# motorfilter.net
KiCad netlist of a schematic drawn in EAGLE
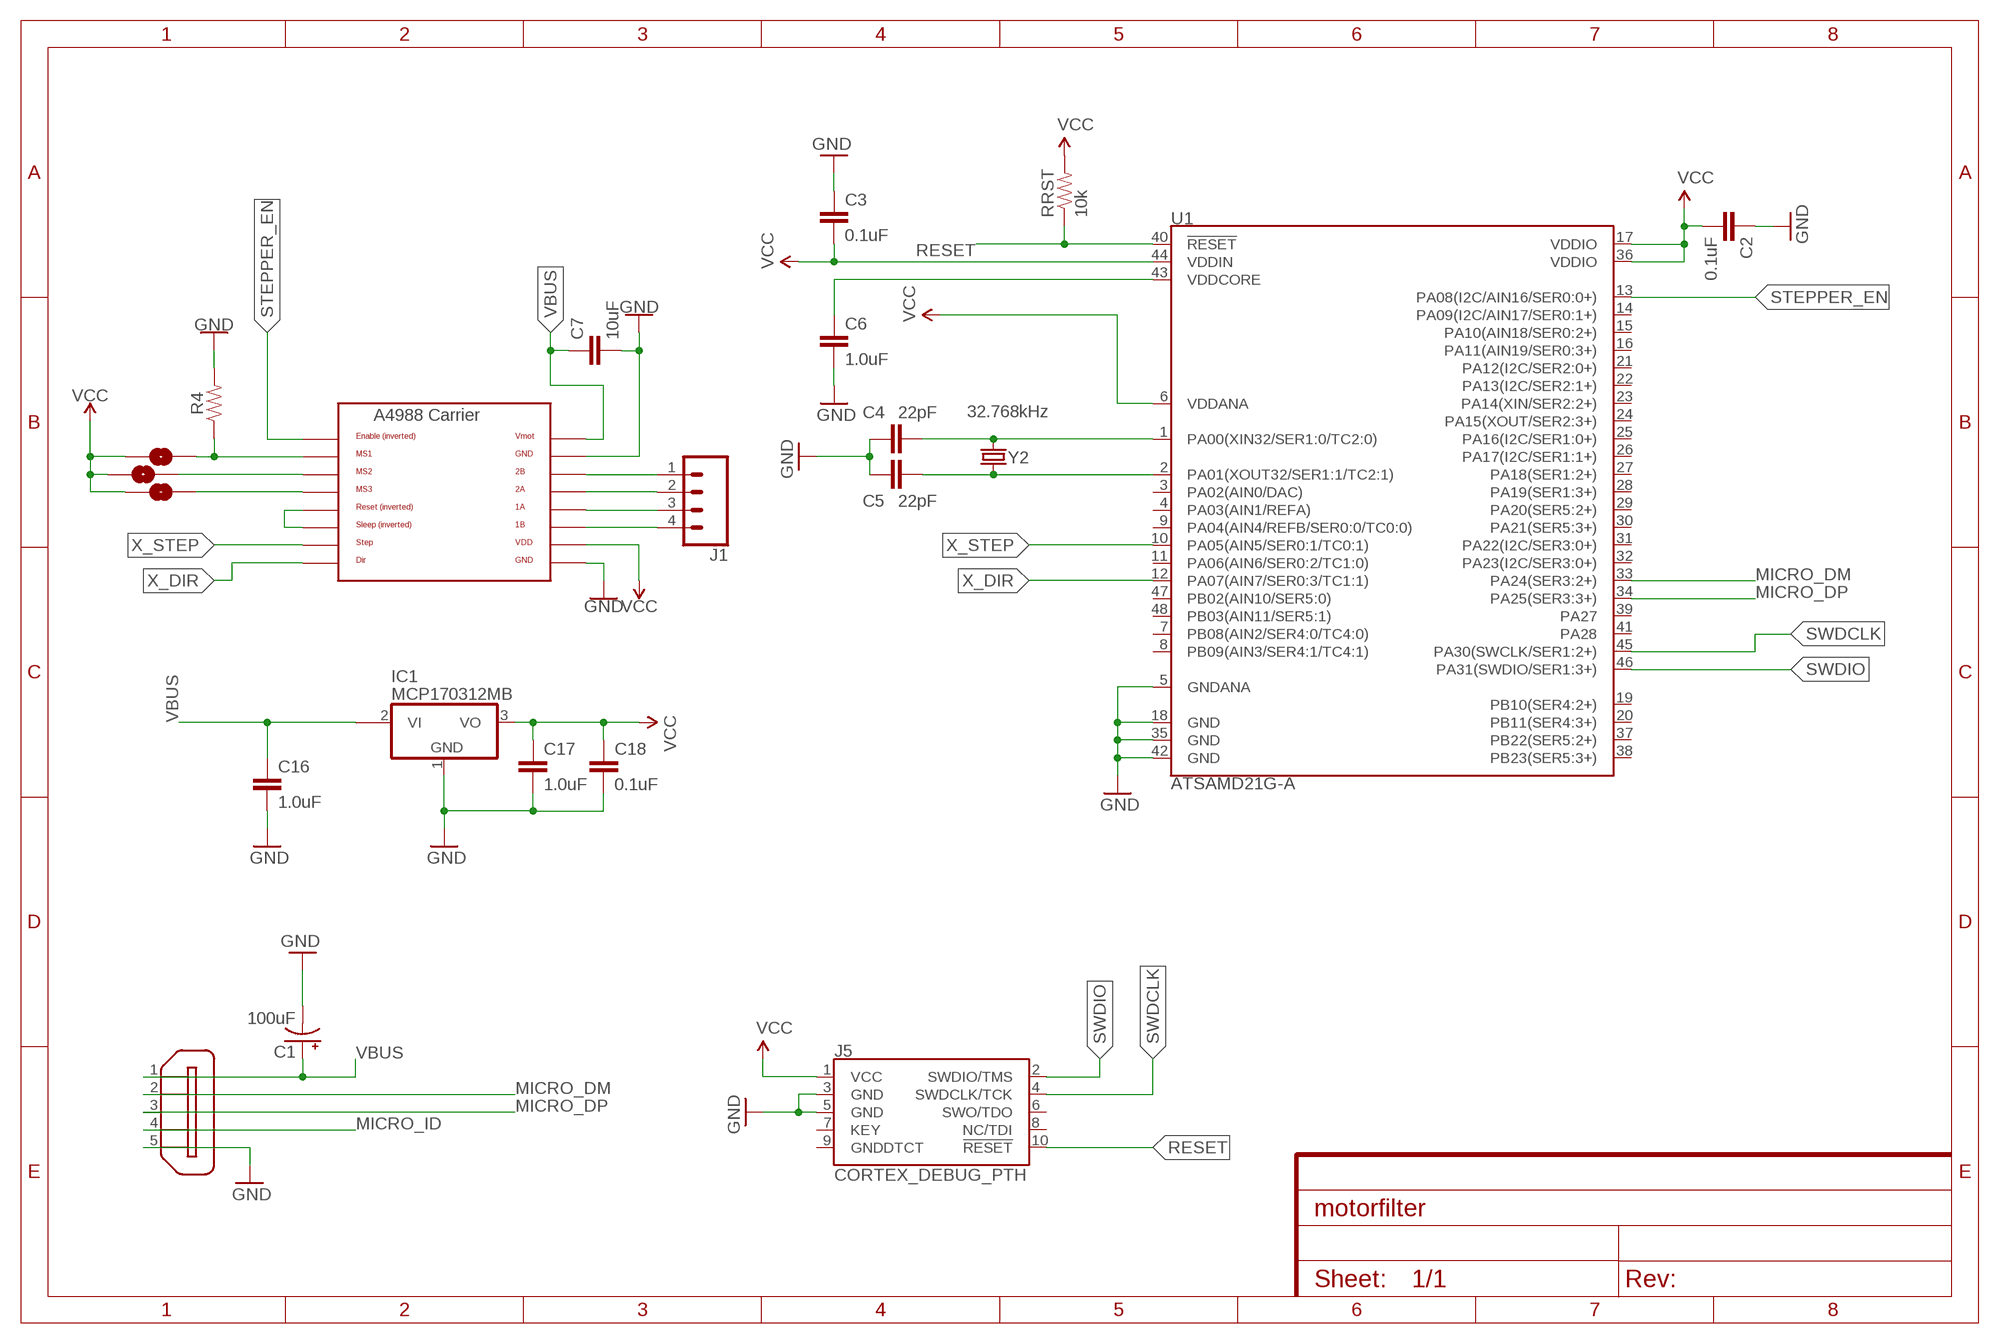
[diagram p0: schematic, sheet 1]

(export (version "E")
  (design (tool "Eeschema 10.0.6"))
  (components
    (comp (ref "C1")
      (value "100uF")
      (footprint "eagle-import:PANASONIC_D")
      (libsource (lib "eagle-import") (part "100UF-POLAR-25V-20%(ELEC)"))
    )
    (comp (ref "C2")
      (value "0.1uF")
      (footprint "eagle-import:0805")
      (libsource (lib "eagle-import") (part "1.0UF-0805-25V-10%"))
    )
    (comp (ref "C3")
      (value "0.1uF")
      (footprint "eagle-import:0805")
      (libsource (lib "eagle-import") (part "1.0UF-0805-25V-10%"))
    )
    (comp (ref "C4")
      (value "22pF")
      (footprint "eagle-import:0805")
      (libsource (lib "eagle-import") (part "CAP0805"))
    )
    (comp (ref "C5")
      (value "22pF")
      (footprint "eagle-import:0805")
      (libsource (lib "eagle-import") (part "CAP0805"))
    )
    (comp (ref "C6")
      (value "1.0uF")
      (footprint "eagle-import:0805")
      (libsource (lib "eagle-import") (part "1.0UF-0805-25V-10%"))
    )
    (comp (ref "C7")
      (value "10uF")
      (footprint "eagle-import:1206")
      (libsource (lib "eagle-import") (part "1.0UF-1206-50V-10%"))
    )
    (comp (ref "C16")
      (value "1.0uF")
      (footprint "eagle-import:0805")
      (libsource (lib "eagle-import") (part "1.0UF-0805-25V-10%"))
    )
    (comp (ref "C17")
      (value "1.0uF")
      (footprint "eagle-import:1206")
      (libsource (lib "eagle-import") (part "1.0UF-1206-50V-10%"))
    )
    (comp (ref "C18")
      (value "0.1uF")
      (footprint "eagle-import:0805")
      (libsource (lib "eagle-import") (part "1.0UF-0805-25V-10%"))
    )
    (comp (ref "IC1")
      (value "MCP170312MB")
      (footprint "eagle-import:SOT89")
      (libsource (lib "eagle-import") (part "MCP1703MB12"))
    )
    (comp (ref "J1")
      (value "CONN_04SCREW")
      (footprint "eagle-import:SCREWTERMINAL-3.5MM-4")
      (libsource (lib "eagle-import") (part "CONN_04SCREW"))
    )
    (comp (ref "J5")
      (value "CORTEX_DEBUG_PTH")
      (footprint "eagle-import:2X5-PTH-1.27MM")
      (libsource (lib "eagle-import") (part "CORTEX_DEBUG_PTH"))
    )
    (comp (ref "JP4")
      (value "JUMPER-SMT_2_NO_SILK_ROUND")
      (footprint "eagle-import:SMT-JUMPER_2_NO_SILK_ROUND")
      (libsource (lib "eagle-import") (part "JUMPER-SMT_2_NO_SILK_ROUND"))
    )
    (comp (ref "JP5")
      (value "JUMPER-SMT_2_NO_SILK_ROUND")
      (footprint "eagle-import:SMT-JUMPER_2_NO_SILK_ROUND")
      (libsource (lib "eagle-import") (part "JUMPER-SMT_2_NO_SILK_ROUND"))
    )
    (comp (ref "JP6")
      (value "JUMPER-SMT_2_NO_SILK_ROUND")
      (footprint "eagle-import:SMT-JUMPER_2_NO_SILK_ROUND")
      (libsource (lib "eagle-import") (part "JUMPER-SMT_2_NO_SILK_ROUND"))
    )
    (comp (ref "R4")
      (value "RESISTOR0805")
      (footprint "eagle-import:0805")
      (libsource (lib "eagle-import") (part "RESISTOR0805"))
    )
    (comp (ref "RRST")
      (value "10k")
      (footprint "eagle-import:0805")
      (libsource (lib "eagle-import") (part "RESISTOR0805-RES"))
    )
    (comp (ref "U$2")
      (value "A4988BREAKOUT")
      (footprint "eagle-import:A4988BREAKOUT")
      (libsource (lib "eagle-import") (part "A4988BREAKOUT"))
    )
    (comp (ref "U1")
      (value "ATSAMD21G-A")
      (footprint "eagle-import:TQFP-48")
      (libsource (lib "eagle-import") (part "ATSAMD21G-A"))
    )
    (comp (ref "X2")
      (value "ZX62D-B-5PA8")
      (footprint "eagle-import:ZX62D-B-5PA8")
      (fields (field (name "MF") "Hirose"))
      (libsource (lib "eagle-import") (part "ZX62D-B-5PA8"))
    )
    (comp (ref "Y2")
      (value "32.768kHz")
      (footprint "eagle-import:CRYSTAL-SMD-3.2X1.5MM")
      (libsource (lib "eagle-import") (part "CRYSTAL3.2X1.5MM"))
    )
  )
  (nets
    (net (code "1") (name "/MICRO_DM") (class "Default")
      (node (ref "U1") (pin "33") (pinfunction "PA24(SER3:2+)_33") (pintype "bidirectional"))
      (node (ref "X2") (pin "2") (pinfunction "2_2") (pintype "passive"))
    )
    (net (code "2") (name "/MICRO_DP") (class "Default")
      (node (ref "U1") (pin "34") (pinfunction "PA25(SER3:3+)_34") (pintype "bidirectional"))
      (node (ref "X2") (pin "3") (pinfunction "3_3") (pintype "passive"))
    )
    (net (code "3") (name "/MICRO_ID") (class "Default")
      (node (ref "X2") (pin "4") (pinfunction "4_4") (pintype "passive"))
    )
    (net (code "4") (name "GND") (class "Default")
      (node (ref "C1") (pin "-") (pinfunction "-_-") (pintype "passive"))
      (node (ref "C16") (pin "2") (pinfunction "2_2") (pintype "passive"))
      (node (ref "C17") (pin "2") (pinfunction "2_2") (pintype "passive"))
      (node (ref "C18") (pin "2") (pinfunction "2_2") (pintype "passive"))
      (node (ref "C2") (pin "1") (pinfunction "1_1") (pintype "passive"))
      (node (ref "C3") (pin "1") (pinfunction "1_1") (pintype "passive"))
      (node (ref "C4") (pin "1") (pinfunction "1_1") (pintype "passive"))
      (node (ref "C5") (pin "1") (pinfunction "1_1") (pintype "passive"))
      (node (ref "C6") (pin "2") (pinfunction "2_2") (pintype "passive"))
      (node (ref "C7") (pin "2") (pinfunction "2_2") (pintype "passive"))
      (node (ref "IC1") (pin "1") (pinfunction "GND_1") (pintype "passive"))
      (node (ref "J5") (pin "3") (pinfunction "GND_3") (pintype "bidirectional"))
      (node (ref "J5") (pin "5") (pinfunction "GND_5") (pintype "bidirectional"))
      (node (ref "R4") (pin "2") (pinfunction "2_2") (pintype "passive"))
      (node (ref "U$2") (pin "GND") (pinfunction "GND_GND") (pintype "power_in"))
      (node (ref "U$2") (pin "GND@0") (pinfunction "GND_GND@0") (pintype "power_in"))
      (node (ref "U1") (pin "18") (pinfunction "GND_18") (pintype "bidirectional"))
      (node (ref "U1") (pin "35") (pinfunction "GND_35") (pintype "bidirectional"))
      (node (ref "U1") (pin "42") (pinfunction "GND_42") (pintype "bidirectional"))
      (node (ref "U1") (pin "5") (pinfunction "GNDANA_5") (pintype "bidirectional"))
      (node (ref "X2") (pin "5") (pinfunction "5_5") (pintype "passive"))
    )
    (net (code "5") (name "Net-(J1-Pad1)") (class "Default")
      (node (ref "J1") (pin "1") (pinfunction "1_1") (pintype "passive"))
      (node (ref "U$2") (pin "2B") (pinfunction "2B_2B") (pintype "output"))
    )
    (net (code "6") (name "Net-(J1-Pad2)") (class "Default")
      (node (ref "J1") (pin "2") (pinfunction "2_2") (pintype "passive"))
      (node (ref "U$2") (pin "2A") (pinfunction "2A_2A") (pintype "output"))
    )
    (net (code "7") (name "Net-(J1-Pad3)") (class "Default")
      (node (ref "J1") (pin "3") (pinfunction "3_3") (pintype "passive"))
      (node (ref "U$2") (pin "1A") (pinfunction "1A_1A") (pintype "output"))
    )
    (net (code "8") (name "Net-(J1-Pad4)") (class "Default")
      (node (ref "J1") (pin "4") (pinfunction "4_4") (pintype "passive"))
      (node (ref "U$2") (pin "1B") (pinfunction "1B_1B") (pintype "output"))
    )
    (net (code "9") (name "Net-(JP4-Pad2)") (class "Default")
      (node (ref "JP4") (pin "2") (pinfunction "2_2") (pintype "passive"))
      (node (ref "R4") (pin "1") (pinfunction "1_1") (pintype "passive"))
      (node (ref "U$2") (pin "MS1") (pinfunction "MS1_MS1") (pintype "input"))
    )
    (net (code "10") (name "Net-(JP5-Pad2)") (class "Default")
      (node (ref "JP5") (pin "2") (pinfunction "2_2") (pintype "passive"))
      (node (ref "U$2") (pin "MS2") (pinfunction "MS2_MS2") (pintype "input"))
    )
    (net (code "11") (name "Net-(JP6-Pad2)") (class "Default")
      (node (ref "JP6") (pin "2") (pinfunction "2_2") (pintype "passive"))
      (node (ref "U$2") (pin "MS3") (pinfunction "MS3_MS3") (pintype "input"))
    )
    (net (code "12") (name "Net-(U$2-SLEEP)") (class "Default")
      (node (ref "U$2") (pin "RST") (pinfunction "RST_RST") (pintype "input"))
      (node (ref "U$2") (pin "SLP") (pinfunction "SLEEP_SLP") (pintype "input"))
    )
    (net (code "13") (name "Net-(U1-PA00(XIN32{slash}SER1:0{slash}TC2:0))") (class "Default")
      (node (ref "C4") (pin "2") (pinfunction "2_2") (pintype "passive"))
      (node (ref "U1") (pin "1") (pinfunction "PA00(XIN32/SER1:0/TC2:0)_1") (pintype "bidirectional"))
      (node (ref "Y2") (pin "P$2") (pinfunction "2_P$2") (pintype "passive"))
    )
    (net (code "14") (name "Net-(U1-PA01(XOUT32{slash}SER1:1{slash}TC2:1))") (class "Default")
      (node (ref "C5") (pin "2") (pinfunction "2_2") (pintype "passive"))
      (node (ref "U1") (pin "2") (pinfunction "PA01(XOUT32/SER1:1/TC2:1)_2") (pintype "bidirectional"))
      (node (ref "Y2") (pin "P$1") (pinfunction "1_P$1") (pintype "passive"))
    )
    (net (code "15") (name "Net-(U1-VDDCORE)") (class "Default")
      (node (ref "C6") (pin "1") (pinfunction "1_1") (pintype "passive"))
      (node (ref "U1") (pin "43") (pinfunction "VDDCORE_43") (pintype "bidirectional"))
    )
    (net (code "16") (name "RESET") (class "Default")
      (node (ref "J5") (pin "10") (pinfunction "~{RESET}_10") (pintype "bidirectional"))
      (node (ref "RRST") (pin "1") (pinfunction "1_1") (pintype "passive"))
      (node (ref "U1") (pin "40") (pinfunction "~{RESET}_40") (pintype "bidirectional"))
    )
    (net (code "17") (name "STEPPER_EN") (class "Default")
      (node (ref "U$2") (pin "EN") (pinfunction "EN_EN") (pintype "input"))
      (node (ref "U1") (pin "13") (pinfunction "PA08(I2C/AIN16/SER0:0+)_13") (pintype "bidirectional"))
    )
    (net (code "18") (name "SWDCLK") (class "Default")
      (node (ref "J5") (pin "4") (pinfunction "SWDCLK/TCK_4") (pintype "bidirectional"))
      (node (ref "U1") (pin "45") (pinfunction "PA30(SWCLK/SER1:2+)_45") (pintype "bidirectional"))
    )
    (net (code "19") (name "SWDIO") (class "Default")
      (node (ref "J5") (pin "2") (pinfunction "SWDIO/TMS_2") (pintype "bidirectional"))
      (node (ref "U1") (pin "46") (pinfunction "PA31(SWDIO/SER1:3+)_46") (pintype "bidirectional"))
    )
    (net (code "20") (name "VBUS") (class "Default")
      (node (ref "C1") (pin "+") (pinfunction "+_+") (pintype "passive"))
      (node (ref "C16") (pin "1") (pinfunction "1_1") (pintype "passive"))
      (node (ref "C7") (pin "1") (pinfunction "1_1") (pintype "passive"))
      (node (ref "IC1") (pin "2@1") (pinfunction "VI1_2@1") (pintype "input"))
      (node (ref "U$2") (pin "VMOT") (pinfunction "VMOT_VMOT") (pintype "power_in"))
      (node (ref "X2") (pin "1") (pinfunction "1_1") (pintype "passive"))
    )
    (net (code "21") (name "VCC") (class "Default")
      (node (ref "C17") (pin "1") (pinfunction "1_1") (pintype "passive"))
      (node (ref "C18") (pin "1") (pinfunction "1_1") (pintype "passive"))
      (node (ref "C2") (pin "2") (pinfunction "2_2") (pintype "passive"))
      (node (ref "C3") (pin "2") (pinfunction "2_2") (pintype "passive"))
      (node (ref "IC1") (pin "3") (pinfunction "VO_3") (pintype "passive"))
      (node (ref "J5") (pin "1") (pinfunction "VCC_1") (pintype "bidirectional"))
      (node (ref "JP4") (pin "1") (pinfunction "1_1") (pintype "passive"))
      (node (ref "JP5") (pin "1") (pinfunction "1_1") (pintype "passive"))
      (node (ref "JP6") (pin "1") (pinfunction "1_1") (pintype "passive"))
      (node (ref "RRST") (pin "2") (pinfunction "2_2") (pintype "passive"))
      (node (ref "U$2") (pin "VDD") (pinfunction "VDD_VDD") (pintype "power_in"))
      (node (ref "U1") (pin "17") (pinfunction "VDDIO_17") (pintype "bidirectional"))
      (node (ref "U1") (pin "36") (pinfunction "VDDIO_36") (pintype "bidirectional"))
      (node (ref "U1") (pin "44") (pinfunction "VDDIN_44") (pintype "bidirectional"))
      (node (ref "U1") (pin "6") (pinfunction "VDDANA_6") (pintype "bidirectional"))
    )
    (net (code "22") (name "X_DIR") (class "Default")
      (node (ref "U$2") (pin "DIR") (pinfunction "DIR_DIR") (pintype "input"))
      (node (ref "U1") (pin "12") (pinfunction "PA07(AIN7/SER0:3/TC1:1)_12") (pintype "bidirectional"))
    )
    (net (code "23") (name "X_STEP") (class "Default")
      (node (ref "U$2") (pin "STEP") (pinfunction "STEP_STEP") (pintype "input"))
      (node (ref "U1") (pin "10") (pinfunction "PA05(AIN5/SER0:1/TC0:1)_10") (pintype "bidirectional"))
    )
    (net (code "24") (name "unconnected-(IC1-VI-Pad2)") (class "Default")
      (node (ref "IC1") (pin "2") (pinfunction "VI_2") (pintype "input"))
    )
    (net (code "25") (name "unconnected-(J5-GNDDTCT-Pad9)") (class "Default")
      (node (ref "J5") (pin "9") (pinfunction "GNDDTCT_9") (pintype "bidirectional"))
    )
    (net (code "26") (name "unconnected-(J5-KEY-Pad7)") (class "Default")
      (node (ref "J5") (pin "7") (pinfunction "KEY_7") (pintype "bidirectional"))
    )
    (net (code "27") (name "unconnected-(J5-NC{slash}TDI-Pad8)") (class "Default")
      (node (ref "J5") (pin "8") (pinfunction "NC/TDI_8") (pintype "bidirectional"))
    )
    (net (code "28") (name "unconnected-(J5-SWO{slash}TDO-Pad6)") (class "Default")
      (node (ref "J5") (pin "6") (pinfunction "SWO/TDO_6") (pintype "bidirectional"))
    )
    (net (code "29") (name "unconnected-(U1-PA02(AIN0{slash}DAC)-Pad3)") (class "Default")
      (node (ref "U1") (pin "3") (pinfunction "PA02(AIN0/DAC)_3") (pintype "bidirectional"))
    )
    (net (code "30") (name "unconnected-(U1-PA03(AIN1{slash}REFA)-Pad4)") (class "Default")
      (node (ref "U1") (pin "4") (pinfunction "PA03(AIN1/REFA)_4") (pintype "bidirectional"))
    )
    (net (code "31") (name "unconnected-(U1-PA04(AIN4{slash}REFB{slash}SER0:0{slash}TC0:0)-Pad9)") (class "Default")
      (node (ref "U1") (pin "9") (pinfunction "PA04(AIN4/REFB/SER0:0/TC0:0)_9") (pintype "bidirectional"))
    )
    (net (code "32") (name "unconnected-(U1-PA06(AIN6{slash}SER0:2{slash}TC1:0)-Pad11)") (class "Default")
      (node (ref "U1") (pin "11") (pinfunction "PA06(AIN6/SER0:2/TC1:0)_11") (pintype "bidirectional"))
    )
    (net (code "33") (name "unconnected-(U1-PA09(I2C{slash}AIN17{slash}SER0:1+)-Pad14)") (class "Default")
      (node (ref "U1") (pin "14") (pinfunction "PA09(I2C/AIN17/SER0:1+)_14") (pintype "bidirectional"))
    )
    (net (code "34") (name "unconnected-(U1-PA10(AIN18{slash}SER0:2+)-Pad15)") (class "Default")
      (node (ref "U1") (pin "15") (pinfunction "PA10(AIN18/SER0:2+)_15") (pintype "bidirectional"))
    )
    (net (code "35") (name "unconnected-(U1-PA11(AIN19{slash}SER0:3+)-Pad16)") (class "Default")
      (node (ref "U1") (pin "16") (pinfunction "PA11(AIN19/SER0:3+)_16") (pintype "bidirectional"))
    )
    (net (code "36") (name "unconnected-(U1-PA12(I2C{slash}SER2:0+)-Pad21)") (class "Default")
      (node (ref "U1") (pin "21") (pinfunction "PA12(I2C/SER2:0+)_21") (pintype "bidirectional"))
    )
    (net (code "37") (name "unconnected-(U1-PA13(I2C{slash}SER2:1+)-Pad22)") (class "Default")
      (node (ref "U1") (pin "22") (pinfunction "PA13(I2C/SER2:1+)_22") (pintype "bidirectional"))
    )
    (net (code "38") (name "unconnected-(U1-PA14(XIN{slash}SER2:2+)-Pad23)") (class "Default")
      (node (ref "U1") (pin "23") (pinfunction "PA14(XIN/SER2:2+)_23") (pintype "bidirectional"))
    )
    (net (code "39") (name "unconnected-(U1-PA15(XOUT{slash}SER2:3+)-Pad24)") (class "Default")
      (node (ref "U1") (pin "24") (pinfunction "PA15(XOUT/SER2:3+)_24") (pintype "bidirectional"))
    )
    (net (code "40") (name "unconnected-(U1-PA16(I2C{slash}SER1:0+)-Pad25)") (class "Default")
      (node (ref "U1") (pin "25") (pinfunction "PA16(I2C/SER1:0+)_25") (pintype "bidirectional"))
    )
    (net (code "41") (name "unconnected-(U1-PA17(I2C{slash}SER1:1+)-Pad26)") (class "Default")
      (node (ref "U1") (pin "26") (pinfunction "PA17(I2C/SER1:1+)_26") (pintype "bidirectional"))
    )
    (net (code "42") (name "unconnected-(U1-PA18(SER1:2+)-Pad27)") (class "Default")
      (node (ref "U1") (pin "27") (pinfunction "PA18(SER1:2+)_27") (pintype "bidirectional"))
    )
    (net (code "43") (name "unconnected-(U1-PA19(SER1:3+)-Pad28)") (class "Default")
      (node (ref "U1") (pin "28") (pinfunction "PA19(SER1:3+)_28") (pintype "bidirectional"))
    )
    (net (code "44") (name "unconnected-(U1-PA20(SER5:2+)-Pad29)") (class "Default")
      (node (ref "U1") (pin "29") (pinfunction "PA20(SER5:2+)_29") (pintype "bidirectional"))
    )
    (net (code "45") (name "unconnected-(U1-PA21(SER5:3+)-Pad30)") (class "Default")
      (node (ref "U1") (pin "30") (pinfunction "PA21(SER5:3+)_30") (pintype "bidirectional"))
    )
    (net (code "46") (name "unconnected-(U1-PA22(I2C{slash}SER3:0+)-Pad31)") (class "Default")
      (node (ref "U1") (pin "31") (pinfunction "PA22(I2C/SER3:0+)_31") (pintype "bidirectional"))
    )
    (net (code "47") (name "unconnected-(U1-PA23(I2C{slash}SER3:0+)-Pad32)") (class "Default")
      (node (ref "U1") (pin "32") (pinfunction "PA23(I2C/SER3:0+)_32") (pintype "bidirectional"))
    )
    (net (code "48") (name "unconnected-(U1-PA27-Pad39)") (class "Default")
      (node (ref "U1") (pin "39") (pinfunction "PA27_39") (pintype "bidirectional"))
    )
    (net (code "49") (name "unconnected-(U1-PA28-Pad41)") (class "Default")
      (node (ref "U1") (pin "41") (pinfunction "PA28_41") (pintype "bidirectional"))
    )
    (net (code "50") (name "unconnected-(U1-PB02(AIN10{slash}SER5:0)-Pad47)") (class "Default")
      (node (ref "U1") (pin "47") (pinfunction "PB02(AIN10/SER5:0)_47") (pintype "bidirectional"))
    )
    (net (code "51") (name "unconnected-(U1-PB03(AIN11{slash}SER5:1)-Pad48)") (class "Default")
      (node (ref "U1") (pin "48") (pinfunction "PB03(AIN11/SER5:1)_48") (pintype "bidirectional"))
    )
    (net (code "52") (name "unconnected-(U1-PB08(AIN2{slash}SER4:0{slash}TC4:0)-Pad7)") (class "Default")
      (node (ref "U1") (pin "7") (pinfunction "PB08(AIN2/SER4:0/TC4:0)_7") (pintype "bidirectional"))
    )
    (net (code "53") (name "unconnected-(U1-PB09(AIN3{slash}SER4:1{slash}TC4:1)-Pad8)") (class "Default")
      (node (ref "U1") (pin "8") (pinfunction "PB09(AIN3/SER4:1/TC4:1)_8") (pintype "bidirectional"))
    )
    (net (code "54") (name "unconnected-(U1-PB10(SER4:2+)-Pad19)") (class "Default")
      (node (ref "U1") (pin "19") (pinfunction "PB10(SER4:2+)_19") (pintype "bidirectional"))
    )
    (net (code "55") (name "unconnected-(U1-PB11(SER4:3+)-Pad20)") (class "Default")
      (node (ref "U1") (pin "20") (pinfunction "PB11(SER4:3+)_20") (pintype "bidirectional"))
    )
    (net (code "56") (name "unconnected-(U1-PB22(SER5:2+)-Pad37)") (class "Default")
      (node (ref "U1") (pin "37") (pinfunction "PB22(SER5:2+)_37") (pintype "bidirectional"))
    )
    (net (code "57") (name "unconnected-(U1-PB23(SER5:3+)-Pad38)") (class "Default")
      (node (ref "U1") (pin "38") (pinfunction "PB23(SER5:3+)_38") (pintype "bidirectional"))
    )
  )
)
